# PCI-104.net
KiCad netlist of a schematic drawn in Altium Designer
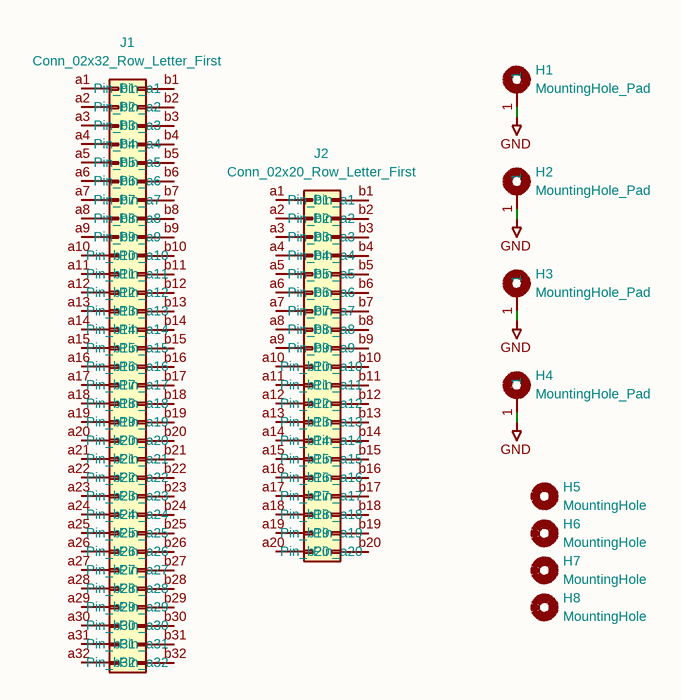
[diagram p0: PCI-104.SchDoc]

(export (version "E")
  (design (tool "Eeschema 10.0.6"))
  (components
    (comp (ref "H1")
      (value "MountingHole_Pad")
      (description "Mounting Hole with connection")
      (libsource (lib "Mechanical") (part "MountingHole_Pad"))
    )
    (comp (ref "H2")
      (value "MountingHole_Pad")
      (description "Mounting Hole with connection")
      (libsource (lib "Mechanical") (part "MountingHole_Pad"))
    )
    (comp (ref "H3")
      (value "MountingHole_Pad")
      (description "Mounting Hole with connection")
      (libsource (lib "Mechanical") (part "MountingHole_Pad"))
    )
    (comp (ref "H4")
      (value "MountingHole_Pad")
      (description "Mounting Hole with connection")
      (libsource (lib "Mechanical") (part "MountingHole_Pad"))
    )
    (comp (ref "H5")
      (value "MountingHole")
      (description "Mounting Hole without connection")
      (libsource (lib "Mechanical") (part "MountingHole"))
    )
    (comp (ref "H6")
      (value "MountingHole")
      (description "Mounting Hole without connection")
      (libsource (lib "Mechanical") (part "MountingHole"))
    )
    (comp (ref "H7")
      (value "MountingHole")
      (description "Mounting Hole without connection")
      (libsource (lib "Mechanical") (part "MountingHole"))
    )
    (comp (ref "H8")
      (value "MountingHole")
      (description "Mounting Hole without connection")
      (libsource (lib "Mechanical") (part "MountingHole"))
    )
    (comp (ref "J1")
      (value "Conn_02x32_Row_Letter_First")
      (libsource (lib "Connector_Generic") (part "Conn_02x32_Row_Letter_First"))
    )
    (comp (ref "J2")
      (value "Conn_02x20_Row_Letter_First")
      (libsource (lib "Connector_Generic") (part "Conn_02x20_Row_Letter_First"))
    )
  )
  (nets
    (net (code "1") (name "GND") (class "Default")
      (node (ref "H1") (pin "1") (pinfunction "1_1") (pintype "passive"))
      (node (ref "H2") (pin "1") (pinfunction "1_1") (pintype "passive"))
      (node (ref "H3") (pin "1") (pinfunction "1_1") (pintype "passive"))
      (node (ref "H4") (pin "1") (pinfunction "1_1") (pintype "passive"))
    )
    (net (code "2") (name "unconnected-(J1-Pin_a1-Pada1)") (class "Default")
      (node (ref "J1") (pin "a1") (pinfunction "Pin_a1_a1") (pintype "passive"))
    )
    (net (code "3") (name "unconnected-(J1-Pin_a2-Pada2)") (class "Default")
      (node (ref "J1") (pin "a2") (pinfunction "Pin_a2_a2") (pintype "passive"))
    )
    (net (code "4") (name "unconnected-(J1-Pin_a3-Pada3)") (class "Default")
      (node (ref "J1") (pin "a3") (pinfunction "Pin_a3_a3") (pintype "passive"))
    )
    (net (code "5") (name "unconnected-(J1-Pin_a4-Pada4)") (class "Default")
      (node (ref "J1") (pin "a4") (pinfunction "Pin_a4_a4") (pintype "passive"))
    )
    (net (code "6") (name "unconnected-(J1-Pin_a5-Pada5)") (class "Default")
      (node (ref "J1") (pin "a5") (pinfunction "Pin_a5_a5") (pintype "passive"))
    )
    (net (code "7") (name "unconnected-(J1-Pin_a6-Pada6)") (class "Default")
      (node (ref "J1") (pin "a6") (pinfunction "Pin_a6_a6") (pintype "passive"))
    )
    (net (code "8") (name "unconnected-(J1-Pin_a7-Pada7)") (class "Default")
      (node (ref "J1") (pin "a7") (pinfunction "Pin_a7_a7") (pintype "passive"))
    )
    (net (code "9") (name "unconnected-(J1-Pin_a8-Pada8)") (class "Default")
      (node (ref "J1") (pin "a8") (pinfunction "Pin_a8_a8") (pintype "passive"))
    )
    (net (code "10") (name "unconnected-(J1-Pin_a9-Pada9)") (class "Default")
      (node (ref "J1") (pin "a9") (pinfunction "Pin_a9_a9") (pintype "passive"))
    )
    (net (code "11") (name "unconnected-(J1-Pin_a10-Pada10)") (class "Default")
      (node (ref "J1") (pin "a10") (pinfunction "Pin_a10_a10") (pintype "passive"))
    )
    (net (code "12") (name "unconnected-(J1-Pin_a11-Pada11)") (class "Default")
      (node (ref "J1") (pin "a11") (pinfunction "Pin_a11_a11") (pintype "passive"))
    )
    (net (code "13") (name "unconnected-(J1-Pin_a12-Pada12)") (class "Default")
      (node (ref "J1") (pin "a12") (pinfunction "Pin_a12_a12") (pintype "passive"))
    )
    (net (code "14") (name "unconnected-(J1-Pin_a13-Pada13)") (class "Default")
      (node (ref "J1") (pin "a13") (pinfunction "Pin_a13_a13") (pintype "passive"))
    )
    (net (code "15") (name "unconnected-(J1-Pin_a14-Pada14)") (class "Default")
      (node (ref "J1") (pin "a14") (pinfunction "Pin_a14_a14") (pintype "passive"))
    )
    (net (code "16") (name "unconnected-(J1-Pin_a15-Pada15)") (class "Default")
      (node (ref "J1") (pin "a15") (pinfunction "Pin_a15_a15") (pintype "passive"))
    )
    (net (code "17") (name "unconnected-(J1-Pin_a16-Pada16)") (class "Default")
      (node (ref "J1") (pin "a16") (pinfunction "Pin_a16_a16") (pintype "passive"))
    )
    (net (code "18") (name "unconnected-(J1-Pin_a17-Pada17)") (class "Default")
      (node (ref "J1") (pin "a17") (pinfunction "Pin_a17_a17") (pintype "passive"))
    )
    (net (code "19") (name "unconnected-(J1-Pin_a18-Pada18)") (class "Default")
      (node (ref "J1") (pin "a18") (pinfunction "Pin_a18_a18") (pintype "passive"))
    )
    (net (code "20") (name "unconnected-(J1-Pin_a19-Pada19)") (class "Default")
      (node (ref "J1") (pin "a19") (pinfunction "Pin_a19_a19") (pintype "passive"))
    )
    (net (code "21") (name "unconnected-(J1-Pin_a20-Pada20)") (class "Default")
      (node (ref "J1") (pin "a20") (pinfunction "Pin_a20_a20") (pintype "passive"))
    )
    (net (code "22") (name "unconnected-(J1-Pin_a21-Pada21)") (class "Default")
      (node (ref "J1") (pin "a21") (pinfunction "Pin_a21_a21") (pintype "passive"))
    )
    (net (code "23") (name "unconnected-(J1-Pin_a22-Pada22)") (class "Default")
      (node (ref "J1") (pin "a22") (pinfunction "Pin_a22_a22") (pintype "passive"))
    )
    (net (code "24") (name "unconnected-(J1-Pin_a23-Pada23)") (class "Default")
      (node (ref "J1") (pin "a23") (pinfunction "Pin_a23_a23") (pintype "passive"))
    )
    (net (code "25") (name "unconnected-(J1-Pin_a24-Pada24)") (class "Default")
      (node (ref "J1") (pin "a24") (pinfunction "Pin_a24_a24") (pintype "passive"))
    )
    (net (code "26") (name "unconnected-(J1-Pin_a25-Pada25)") (class "Default")
      (node (ref "J1") (pin "a25") (pinfunction "Pin_a25_a25") (pintype "passive"))
    )
    (net (code "27") (name "unconnected-(J1-Pin_a26-Pada26)") (class "Default")
      (node (ref "J1") (pin "a26") (pinfunction "Pin_a26_a26") (pintype "passive"))
    )
    (net (code "28") (name "unconnected-(J1-Pin_a27-Pada27)") (class "Default")
      (node (ref "J1") (pin "a27") (pinfunction "Pin_a27_a27") (pintype "passive"))
    )
    (net (code "29") (name "unconnected-(J1-Pin_a28-Pada28)") (class "Default")
      (node (ref "J1") (pin "a28") (pinfunction "Pin_a28_a28") (pintype "passive"))
    )
    (net (code "30") (name "unconnected-(J1-Pin_a29-Pada29)") (class "Default")
      (node (ref "J1") (pin "a29") (pinfunction "Pin_a29_a29") (pintype "passive"))
    )
    (net (code "31") (name "unconnected-(J1-Pin_a30-Pada30)") (class "Default")
      (node (ref "J1") (pin "a30") (pinfunction "Pin_a30_a30") (pintype "passive"))
    )
    (net (code "32") (name "unconnected-(J1-Pin_a31-Pada31)") (class "Default")
      (node (ref "J1") (pin "a31") (pinfunction "Pin_a31_a31") (pintype "passive"))
    )
    (net (code "33") (name "unconnected-(J1-Pin_a32-Pada32)") (class "Default")
      (node (ref "J1") (pin "a32") (pinfunction "Pin_a32_a32") (pintype "passive"))
    )
    (net (code "34") (name "unconnected-(J1-Pin_b1-Padb1)") (class "Default")
      (node (ref "J1") (pin "b1") (pinfunction "Pin_b1_b1") (pintype "passive"))
    )
    (net (code "35") (name "unconnected-(J1-Pin_b2-Padb2)") (class "Default")
      (node (ref "J1") (pin "b2") (pinfunction "Pin_b2_b2") (pintype "passive"))
    )
    (net (code "36") (name "unconnected-(J1-Pin_b3-Padb3)") (class "Default")
      (node (ref "J1") (pin "b3") (pinfunction "Pin_b3_b3") (pintype "passive"))
    )
    (net (code "37") (name "unconnected-(J1-Pin_b4-Padb4)") (class "Default")
      (node (ref "J1") (pin "b4") (pinfunction "Pin_b4_b4") (pintype "passive"))
    )
    (net (code "38") (name "unconnected-(J1-Pin_b5-Padb5)") (class "Default")
      (node (ref "J1") (pin "b5") (pinfunction "Pin_b5_b5") (pintype "passive"))
    )
    (net (code "39") (name "unconnected-(J1-Pin_b6-Padb6)") (class "Default")
      (node (ref "J1") (pin "b6") (pinfunction "Pin_b6_b6") (pintype "passive"))
    )
    (net (code "40") (name "unconnected-(J1-Pin_b7-Padb7)") (class "Default")
      (node (ref "J1") (pin "b7") (pinfunction "Pin_b7_b7") (pintype "passive"))
    )
    (net (code "41") (name "unconnected-(J1-Pin_b8-Padb8)") (class "Default")
      (node (ref "J1") (pin "b8") (pinfunction "Pin_b8_b8") (pintype "passive"))
    )
    (net (code "42") (name "unconnected-(J1-Pin_b9-Padb9)") (class "Default")
      (node (ref "J1") (pin "b9") (pinfunction "Pin_b9_b9") (pintype "passive"))
    )
    (net (code "43") (name "unconnected-(J1-Pin_b10-Padb10)") (class "Default")
      (node (ref "J1") (pin "b10") (pinfunction "Pin_b10_b10") (pintype "passive"))
    )
    (net (code "44") (name "unconnected-(J1-Pin_b11-Padb11)") (class "Default")
      (node (ref "J1") (pin "b11") (pinfunction "Pin_b11_b11") (pintype "passive"))
    )
    (net (code "45") (name "unconnected-(J1-Pin_b12-Padb12)") (class "Default")
      (node (ref "J1") (pin "b12") (pinfunction "Pin_b12_b12") (pintype "passive"))
    )
    (net (code "46") (name "unconnected-(J1-Pin_b13-Padb13)") (class "Default")
      (node (ref "J1") (pin "b13") (pinfunction "Pin_b13_b13") (pintype "passive"))
    )
    (net (code "47") (name "unconnected-(J1-Pin_b14-Padb14)") (class "Default")
      (node (ref "J1") (pin "b14") (pinfunction "Pin_b14_b14") (pintype "passive"))
    )
    (net (code "48") (name "unconnected-(J1-Pin_b15-Padb15)") (class "Default")
      (node (ref "J1") (pin "b15") (pinfunction "Pin_b15_b15") (pintype "passive"))
    )
    (net (code "49") (name "unconnected-(J1-Pin_b16-Padb16)") (class "Default")
      (node (ref "J1") (pin "b16") (pinfunction "Pin_b16_b16") (pintype "passive"))
    )
    (net (code "50") (name "unconnected-(J1-Pin_b17-Padb17)") (class "Default")
      (node (ref "J1") (pin "b17") (pinfunction "Pin_b17_b17") (pintype "passive"))
    )
    (net (code "51") (name "unconnected-(J1-Pin_b18-Padb18)") (class "Default")
      (node (ref "J1") (pin "b18") (pinfunction "Pin_b18_b18") (pintype "passive"))
    )
    (net (code "52") (name "unconnected-(J1-Pin_b19-Padb19)") (class "Default")
      (node (ref "J1") (pin "b19") (pinfunction "Pin_b19_b19") (pintype "passive"))
    )
    (net (code "53") (name "unconnected-(J1-Pin_b20-Padb20)") (class "Default")
      (node (ref "J1") (pin "b20") (pinfunction "Pin_b20_b20") (pintype "passive"))
    )
    (net (code "54") (name "unconnected-(J1-Pin_b21-Padb21)") (class "Default")
      (node (ref "J1") (pin "b21") (pinfunction "Pin_b21_b21") (pintype "passive"))
    )
    (net (code "55") (name "unconnected-(J1-Pin_b22-Padb22)") (class "Default")
      (node (ref "J1") (pin "b22") (pinfunction "Pin_b22_b22") (pintype "passive"))
    )
    (net (code "56") (name "unconnected-(J1-Pin_b23-Padb23)") (class "Default")
      (node (ref "J1") (pin "b23") (pinfunction "Pin_b23_b23") (pintype "passive"))
    )
    (net (code "57") (name "unconnected-(J1-Pin_b24-Padb24)") (class "Default")
      (node (ref "J1") (pin "b24") (pinfunction "Pin_b24_b24") (pintype "passive"))
    )
    (net (code "58") (name "unconnected-(J1-Pin_b25-Padb25)") (class "Default")
      (node (ref "J1") (pin "b25") (pinfunction "Pin_b25_b25") (pintype "passive"))
    )
    (net (code "59") (name "unconnected-(J1-Pin_b26-Padb26)") (class "Default")
      (node (ref "J1") (pin "b26") (pinfunction "Pin_b26_b26") (pintype "passive"))
    )
    (net (code "60") (name "unconnected-(J1-Pin_b27-Padb27)") (class "Default")
      (node (ref "J1") (pin "b27") (pinfunction "Pin_b27_b27") (pintype "passive"))
    )
    (net (code "61") (name "unconnected-(J1-Pin_b28-Padb28)") (class "Default")
      (node (ref "J1") (pin "b28") (pinfunction "Pin_b28_b28") (pintype "passive"))
    )
    (net (code "62") (name "unconnected-(J1-Pin_b29-Padb29)") (class "Default")
      (node (ref "J1") (pin "b29") (pinfunction "Pin_b29_b29") (pintype "passive"))
    )
    (net (code "63") (name "unconnected-(J1-Pin_b30-Padb30)") (class "Default")
      (node (ref "J1") (pin "b30") (pinfunction "Pin_b30_b30") (pintype "passive"))
    )
    (net (code "64") (name "unconnected-(J1-Pin_b31-Padb31)") (class "Default")
      (node (ref "J1") (pin "b31") (pinfunction "Pin_b31_b31") (pintype "passive"))
    )
    (net (code "65") (name "unconnected-(J1-Pin_b32-Padb32)") (class "Default")
      (node (ref "J1") (pin "b32") (pinfunction "Pin_b32_b32") (pintype "passive"))
    )
    (net (code "66") (name "unconnected-(J2-Pin_a1-Pada1)") (class "Default")
      (node (ref "J2") (pin "a1") (pinfunction "Pin_a1_a1") (pintype "passive"))
    )
    (net (code "67") (name "unconnected-(J2-Pin_a2-Pada2)") (class "Default")
      (node (ref "J2") (pin "a2") (pinfunction "Pin_a2_a2") (pintype "passive"))
    )
    (net (code "68") (name "unconnected-(J2-Pin_a3-Pada3)") (class "Default")
      (node (ref "J2") (pin "a3") (pinfunction "Pin_a3_a3") (pintype "passive"))
    )
    (net (code "69") (name "unconnected-(J2-Pin_a4-Pada4)") (class "Default")
      (node (ref "J2") (pin "a4") (pinfunction "Pin_a4_a4") (pintype "passive"))
    )
    (net (code "70") (name "unconnected-(J2-Pin_a5-Pada5)") (class "Default")
      (node (ref "J2") (pin "a5") (pinfunction "Pin_a5_a5") (pintype "passive"))
    )
    (net (code "71") (name "unconnected-(J2-Pin_a6-Pada6)") (class "Default")
      (node (ref "J2") (pin "a6") (pinfunction "Pin_a6_a6") (pintype "passive"))
    )
    (net (code "72") (name "unconnected-(J2-Pin_a7-Pada7)") (class "Default")
      (node (ref "J2") (pin "a7") (pinfunction "Pin_a7_a7") (pintype "passive"))
    )
    (net (code "73") (name "unconnected-(J2-Pin_a8-Pada8)") (class "Default")
      (node (ref "J2") (pin "a8") (pinfunction "Pin_a8_a8") (pintype "passive"))
    )
    (net (code "74") (name "unconnected-(J2-Pin_a9-Pada9)") (class "Default")
      (node (ref "J2") (pin "a9") (pinfunction "Pin_a9_a9") (pintype "passive"))
    )
    (net (code "75") (name "unconnected-(J2-Pin_a10-Pada10)") (class "Default")
      (node (ref "J2") (pin "a10") (pinfunction "Pin_a10_a10") (pintype "passive"))
    )
    (net (code "76") (name "unconnected-(J2-Pin_a11-Pada11)") (class "Default")
      (node (ref "J2") (pin "a11") (pinfunction "Pin_a11_a11") (pintype "passive"))
    )
    (net (code "77") (name "unconnected-(J2-Pin_a12-Pada12)") (class "Default")
      (node (ref "J2") (pin "a12") (pinfunction "Pin_a12_a12") (pintype "passive"))
    )
    (net (code "78") (name "unconnected-(J2-Pin_a13-Pada13)") (class "Default")
      (node (ref "J2") (pin "a13") (pinfunction "Pin_a13_a13") (pintype "passive"))
    )
    (net (code "79") (name "unconnected-(J2-Pin_a14-Pada14)") (class "Default")
      (node (ref "J2") (pin "a14") (pinfunction "Pin_a14_a14") (pintype "passive"))
    )
    (net (code "80") (name "unconnected-(J2-Pin_a15-Pada15)") (class "Default")
      (node (ref "J2") (pin "a15") (pinfunction "Pin_a15_a15") (pintype "passive"))
    )
    (net (code "81") (name "unconnected-(J2-Pin_a16-Pada16)") (class "Default")
      (node (ref "J2") (pin "a16") (pinfunction "Pin_a16_a16") (pintype "passive"))
    )
    (net (code "82") (name "unconnected-(J2-Pin_a17-Pada17)") (class "Default")
      (node (ref "J2") (pin "a17") (pinfunction "Pin_a17_a17") (pintype "passive"))
    )
    (net (code "83") (name "unconnected-(J2-Pin_a18-Pada18)") (class "Default")
      (node (ref "J2") (pin "a18") (pinfunction "Pin_a18_a18") (pintype "passive"))
    )
    (net (code "84") (name "unconnected-(J2-Pin_a19-Pada19)") (class "Default")
      (node (ref "J2") (pin "a19") (pinfunction "Pin_a19_a19") (pintype "passive"))
    )
    (net (code "85") (name "unconnected-(J2-Pin_a20-Pada20)") (class "Default")
      (node (ref "J2") (pin "a20") (pinfunction "Pin_a20_a20") (pintype "passive"))
    )
    (net (code "86") (name "unconnected-(J2-Pin_b1-Padb1)") (class "Default")
      (node (ref "J2") (pin "b1") (pinfunction "Pin_b1_b1") (pintype "passive"))
    )
    (net (code "87") (name "unconnected-(J2-Pin_b2-Padb2)") (class "Default")
      (node (ref "J2") (pin "b2") (pinfunction "Pin_b2_b2") (pintype "passive"))
    )
    (net (code "88") (name "unconnected-(J2-Pin_b3-Padb3)") (class "Default")
      (node (ref "J2") (pin "b3") (pinfunction "Pin_b3_b3") (pintype "passive"))
    )
    (net (code "89") (name "unconnected-(J2-Pin_b4-Padb4)") (class "Default")
      (node (ref "J2") (pin "b4") (pinfunction "Pin_b4_b4") (pintype "passive"))
    )
    (net (code "90") (name "unconnected-(J2-Pin_b5-Padb5)") (class "Default")
      (node (ref "J2") (pin "b5") (pinfunction "Pin_b5_b5") (pintype "passive"))
    )
    (net (code "91") (name "unconnected-(J2-Pin_b6-Padb6)") (class "Default")
      (node (ref "J2") (pin "b6") (pinfunction "Pin_b6_b6") (pintype "passive"))
    )
    (net (code "92") (name "unconnected-(J2-Pin_b7-Padb7)") (class "Default")
      (node (ref "J2") (pin "b7") (pinfunction "Pin_b7_b7") (pintype "passive"))
    )
    (net (code "93") (name "unconnected-(J2-Pin_b8-Padb8)") (class "Default")
      (node (ref "J2") (pin "b8") (pinfunction "Pin_b8_b8") (pintype "passive"))
    )
    (net (code "94") (name "unconnected-(J2-Pin_b9-Padb9)") (class "Default")
      (node (ref "J2") (pin "b9") (pinfunction "Pin_b9_b9") (pintype "passive"))
    )
    (net (code "95") (name "unconnected-(J2-Pin_b10-Padb10)") (class "Default")
      (node (ref "J2") (pin "b10") (pinfunction "Pin_b10_b10") (pintype "passive"))
    )
    (net (code "96") (name "unconnected-(J2-Pin_b11-Padb11)") (class "Default")
      (node (ref "J2") (pin "b11") (pinfunction "Pin_b11_b11") (pintype "passive"))
    )
    (net (code "97") (name "unconnected-(J2-Pin_b12-Padb12)") (class "Default")
      (node (ref "J2") (pin "b12") (pinfunction "Pin_b12_b12") (pintype "passive"))
    )
    (net (code "98") (name "unconnected-(J2-Pin_b13-Padb13)") (class "Default")
      (node (ref "J2") (pin "b13") (pinfunction "Pin_b13_b13") (pintype "passive"))
    )
    (net (code "99") (name "unconnected-(J2-Pin_b14-Padb14)") (class "Default")
      (node (ref "J2") (pin "b14") (pinfunction "Pin_b14_b14") (pintype "passive"))
    )
    (net (code "100") (name "unconnected-(J2-Pin_b15-Padb15)") (class "Default")
      (node (ref "J2") (pin "b15") (pinfunction "Pin_b15_b15") (pintype "passive"))
    )
    (net (code "101") (name "unconnected-(J2-Pin_b16-Padb16)") (class "Default")
      (node (ref "J2") (pin "b16") (pinfunction "Pin_b16_b16") (pintype "passive"))
    )
    (net (code "102") (name "unconnected-(J2-Pin_b17-Padb17)") (class "Default")
      (node (ref "J2") (pin "b17") (pinfunction "Pin_b17_b17") (pintype "passive"))
    )
    (net (code "103") (name "unconnected-(J2-Pin_b18-Padb18)") (class "Default")
      (node (ref "J2") (pin "b18") (pinfunction "Pin_b18_b18") (pintype "passive"))
    )
    (net (code "104") (name "unconnected-(J2-Pin_b19-Padb19)") (class "Default")
      (node (ref "J2") (pin "b19") (pinfunction "Pin_b19_b19") (pintype "passive"))
    )
    (net (code "105") (name "unconnected-(J2-Pin_b20-Padb20)") (class "Default")
      (node (ref "J2") (pin "b20") (pinfunction "Pin_b20_b20") (pintype "passive"))
    )
  )
)
